# design.net
KiCad netlist of a schematic drawn in EasyEDA
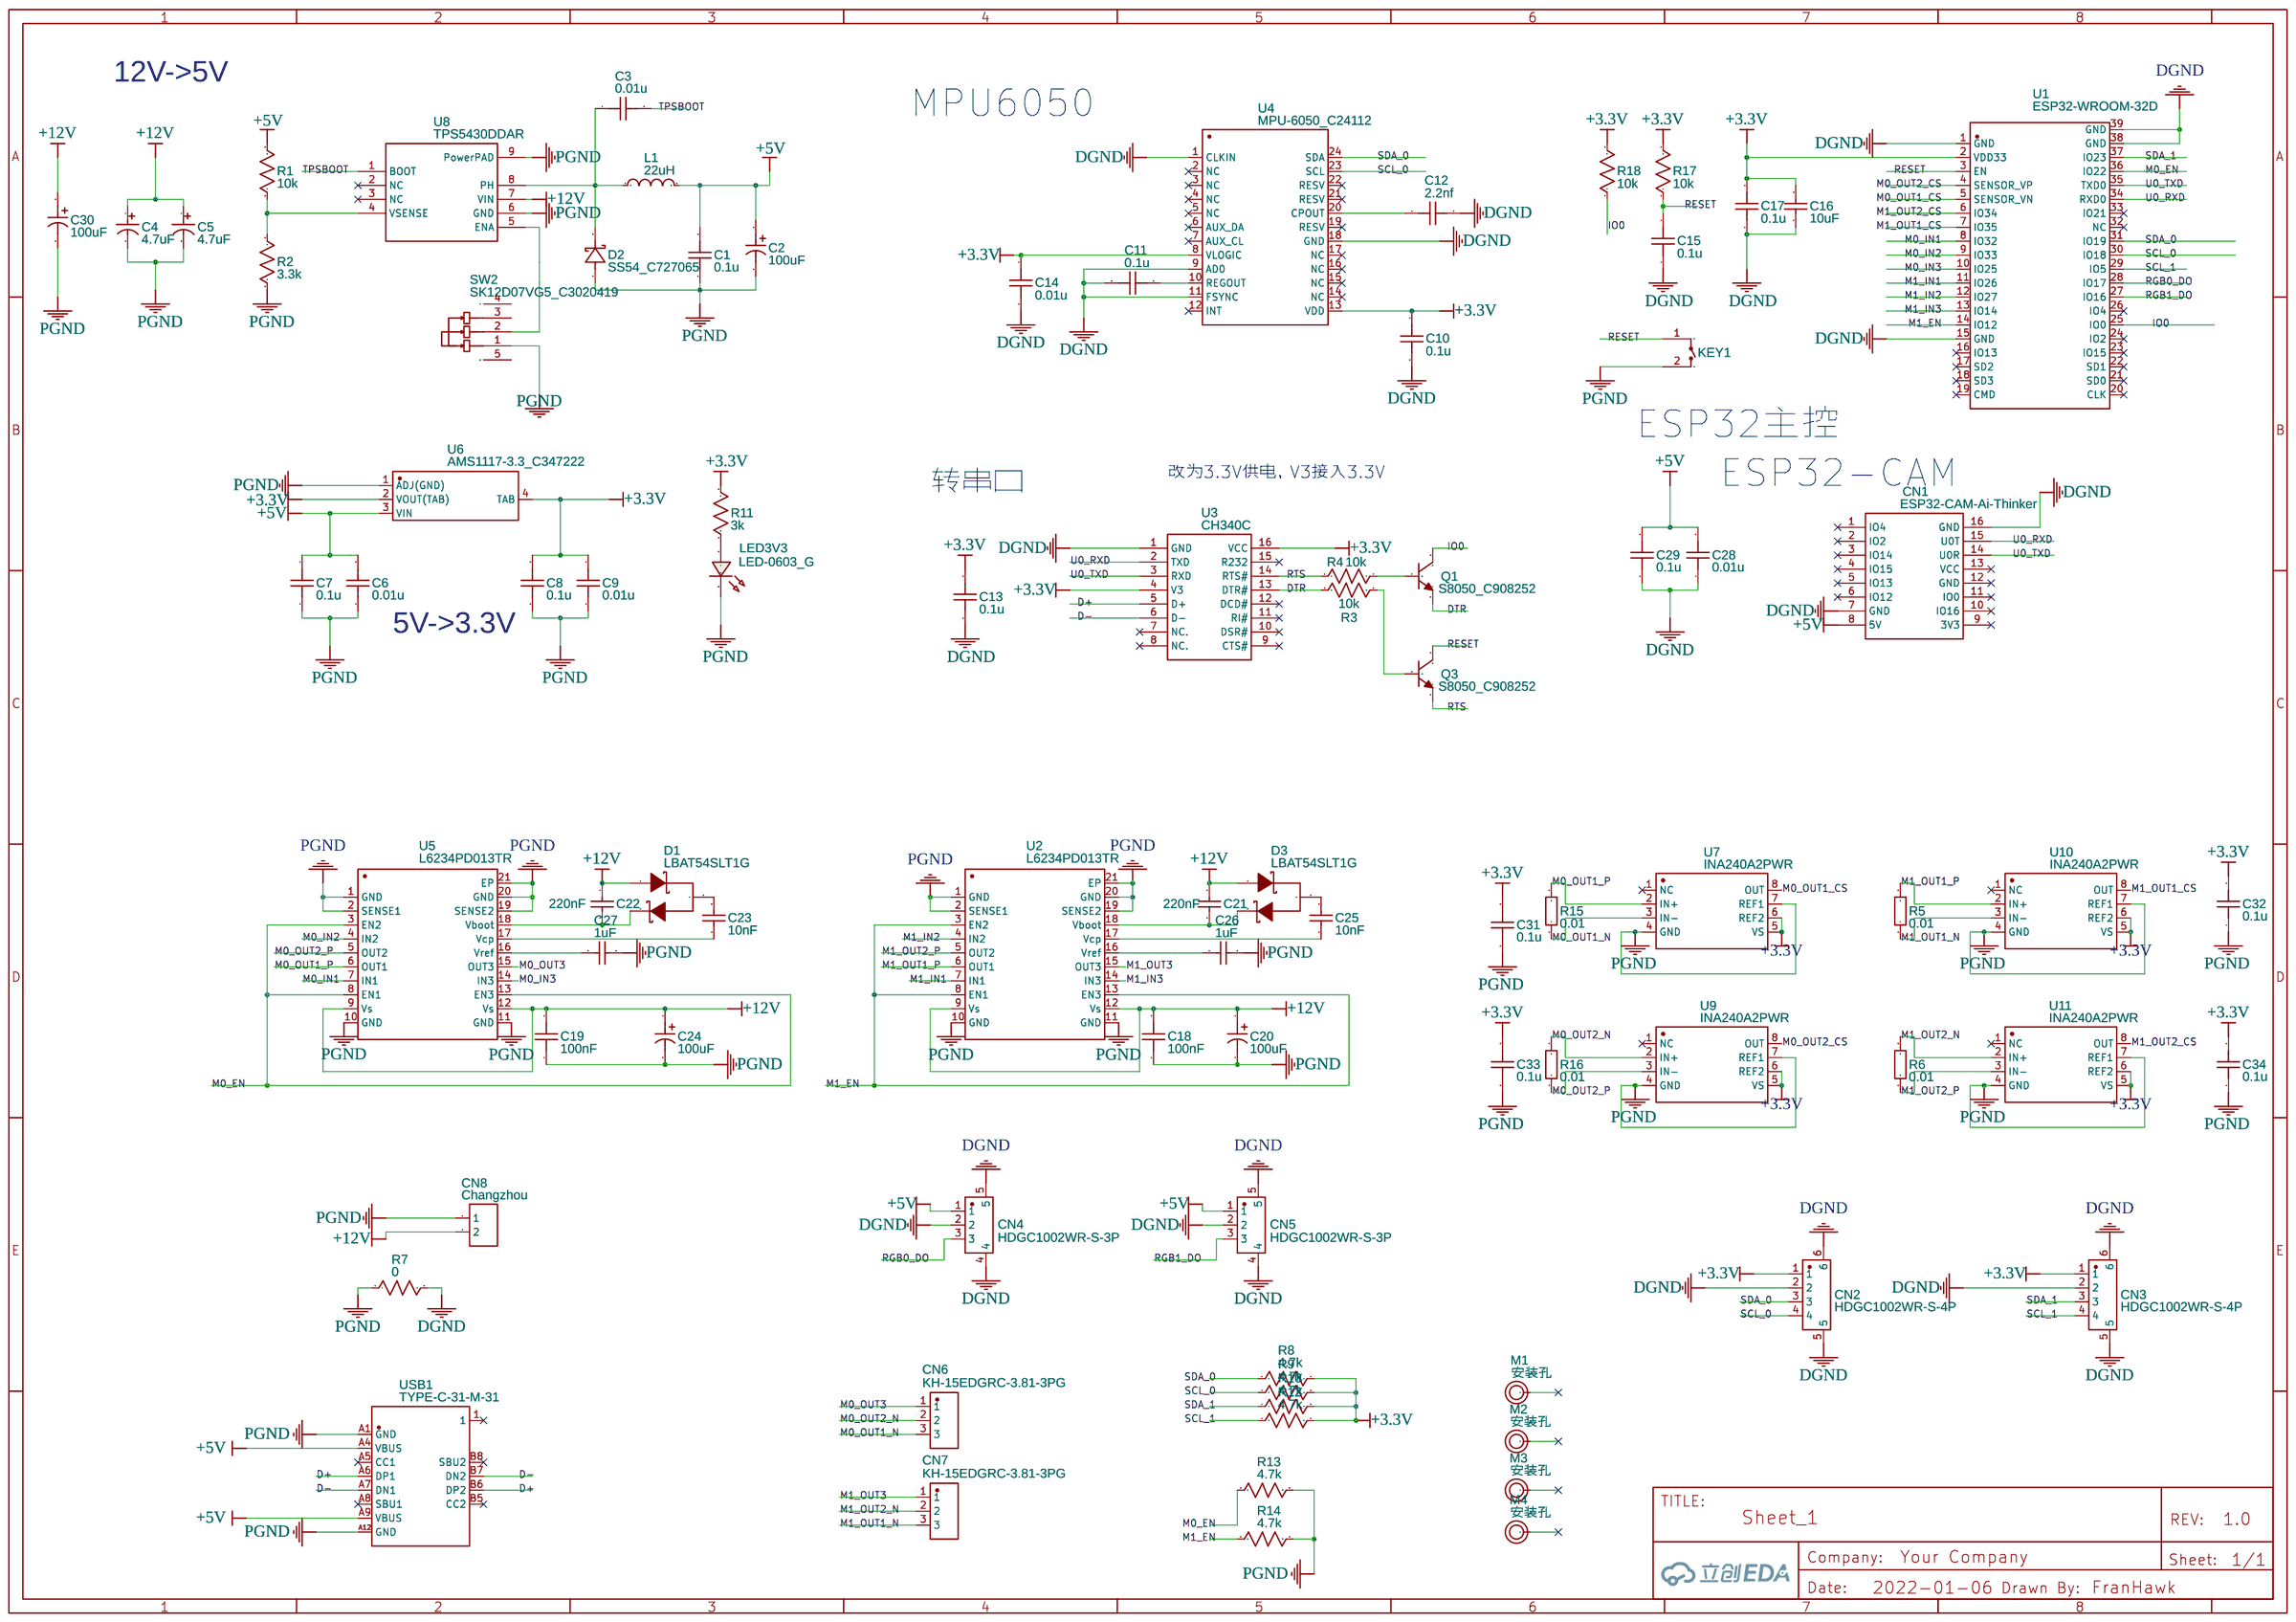
[diagram p0: schematic sheet]

(export (version "E")
  (design (tool "Eeschema 10.0.6"))
  (components
    (comp (ref "C1") (value "0.1u") (libsource (lib "") (part "C_0603_US")))
    (comp (ref "C2")
      (value "100uF")
      (fields
        (field (name "BOM_Manufacturer Part") "LZ101M0801013PE3")
        (field (name "BOM_Supplier Part") "C2847237")
      )
      (libsource (lib "") (part "LZ101M0801013PE3"))
    )
    (comp (ref "C3") (value "0.01u") (libsource (lib "") (part "C_0603_US_1")))
    (comp (ref "C4")
      (value "4.7uF")
      (fields
        (field (name "BOM_Manufacturer Part") "4.7uF 50V 5*11")
        (field (name "BOM_Supplier Part") "C43344")
      )
      (libsource (lib "") (part "4.7uF 50V 5*11"))
    )
    (comp (ref "C5")
      (value "4.7uF")
      (fields
        (field (name "BOM_Manufacturer Part") "4.7uF 50V 5*11")
        (field (name "BOM_Supplier Part") "C43344")
      )
      (libsource (lib "") (part "4.7uF 50V 5*11"))
    )
    (comp (ref "C6") (value "0.01u") (libsource (lib "") (part "C_0603_US")))
    (comp (ref "C7") (value "0.1u") (libsource (lib "") (part "C_0603_US")))
    (comp (ref "C8") (value "0.1u") (libsource (lib "") (part "C_0603_US")))
    (comp (ref "C9") (value "0.01u") (libsource (lib "") (part "C_0603_US")))
    (comp (ref "C10") (value "0.1u") (libsource (lib "") (part "C_0603_US_3")))
    (comp (ref "C11") (value "0.1u") (libsource (lib "") (part "C_0603_US_2")))
    (comp (ref "C12") (value "2.2nf") (libsource (lib "") (part "C_0603_US_1")))
    (comp (ref "C13") (value "0.1u") (libsource (lib "") (part "C_0603_US")))
    (comp (ref "C14") (value "0.01u") (libsource (lib "") (part "C_0603_US_3")))
    (comp (ref "C15") (value "0.1u") (libsource (lib "") (part "C_0603_US")))
    (comp (ref "C16")
      (value "10uF")
      (fields
        (field (name "BOM_Manufacturer Part") "CL31A106KAHNNNE")
        (field (name "BOM_Supplier Part") "C9807")
      )
      (libsource (lib "") (part "CL31A106KAHNNNE"))
    )
    (comp (ref "C17") (value "0.1u") (libsource (lib "") (part "C_0603_US")))
    (comp (ref "C18")
      (value "100nF")
      (fields
        (field (name "BOM_Manufacturer Part") "C0805X104K101T")
        (field (name "BOM_Supplier Part") "C485772")
      )
      (libsource (lib "") (part "C0805X104K101T_C485772"))
    )
    (comp (ref "C19")
      (value "100nF")
      (fields
        (field (name "BOM_Manufacturer Part") "C0805X104K101T")
        (field (name "BOM_Supplier Part") "C485772")
      )
      (libsource (lib "") (part "C0805X104K101T_C485772"))
    )
    (comp (ref "C20")
      (value "100uF")
      (fields
        (field (name "BOM_Manufacturer Part") "LZ101M0801013PE3")
        (field (name "BOM_Supplier Part") "C2847237")
      )
      (libsource (lib "") (part "LZ101M0801013PE3"))
    )
    (comp (ref "C21")
      (value "220nF")
      (fields
        (field (name "BOM_Manufacturer Part") "CL21B224KBFNNNE")
        (field (name "BOM_Supplier Part") "C5378")
      )
      (libsource (lib "") (part "CL21B224KBFNNNE"))
    )
    (comp (ref "C22")
      (value "220nF")
      (fields
        (field (name "BOM_Manufacturer Part") "CL21B224KBFNNNE")
        (field (name "BOM_Supplier Part") "C5378")
      )
      (libsource (lib "") (part "CL21B224KBFNNNE"))
    )
    (comp (ref "C23")
      (value "10nF")
      (fields
        (field (name "BOM_Manufacturer Part") "CL21A106KAYNNNE")
        (field (name "BOM_Supplier Part") "C15850")
      )
      (libsource (lib "") (part "CL21A106KAYNNNE"))
    )
    (comp (ref "C24")
      (value "100uF")
      (fields
        (field (name "BOM_Manufacturer Part") "LZ101M0801013PE3")
        (field (name "BOM_Supplier Part") "C2847237")
      )
      (libsource (lib "") (part "LZ101M0801013PE3"))
    )
    (comp (ref "C25")
      (value "10nF")
      (fields
        (field (name "BOM_Manufacturer Part") "CL21A106KAYNNNE")
        (field (name "BOM_Supplier Part") "C15850")
      )
      (libsource (lib "") (part "CL21A106KAYNNNE"))
    )
    (comp (ref "C26")
      (value "1uF")
      (fields
        (field (name "BOM_Manufacturer Part") "CL21B105KBFNNNE")
        (field (name "BOM_Supplier Part") "C28323")
      )
      (libsource (lib "") (part "CL21B105KBFNNNE"))
    )
    (comp (ref "C27")
      (value "1uF")
      (fields
        (field (name "BOM_Manufacturer Part") "CL21B105KBFNNNE")
        (field (name "BOM_Supplier Part") "C28323")
      )
      (libsource (lib "") (part "CL21B105KBFNNNE"))
    )
    (comp (ref "C28") (value "0.01u") (libsource (lib "") (part "C_0603_US")))
    (comp (ref "C29") (value "0.1u") (libsource (lib "") (part "C_0603_US")))
    (comp (ref "C30")
      (value "100uF")
      (fields
        (field (name "BOM_Manufacturer Part") "LZ101M0801013PE3")
        (field (name "BOM_Supplier Part") "C2847237")
      )
      (libsource (lib "") (part "LZ101M0801013PE3"))
    )
    (comp (ref "C31") (value "0.1u") (libsource (lib "") (part "C_0603_US")))
    (comp (ref "C32") (value "0.1u") (libsource (lib "") (part "C_0603_US")))
    (comp (ref "C33") (value "0.1u") (libsource (lib "") (part "C_0603_US")))
    (comp (ref "C34") (value "0.1u") (libsource (lib "") (part "C_0603_US")))
    (comp (ref "CN1")
      (value "ESP32-CAM-Ai-Thinker")
      (fields (field (name "BOM_Manufacturer Part") "ESP32-CAM"))
      (libsource (lib "") (part "ESP32-CAM-Ai-Thinker"))
    )
    (comp (ref "CN2")
      (value "HDGC1002WR-S-4P")
      (fields (field (name "BOM_Supplier Part") "C2936214"))
      (libsource (lib "") (part "HDGC1002WR-S-4P"))
    )
    (comp (ref "CN3")
      (value "HDGC1002WR-S-4P")
      (fields (field (name "BOM_Supplier Part") "C2936214"))
      (libsource (lib "") (part "HDGC1002WR-S-4P"))
    )
    (comp (ref "CN4")
      (value "HDGC1002WR-S-3P")
      (fields (field (name "BOM_Supplier Part") "C2936213"))
      (libsource (lib "") (part "HDGC1002WR-S-3P"))
    )
    (comp (ref "CN5")
      (value "HDGC1002WR-S-3P")
      (fields (field (name "BOM_Supplier Part") "C2936213"))
      (libsource (lib "") (part "HDGC1002WR-S-3P"))
    )
    (comp (ref "CN6")
      (value "KH-15EDGRC-3.81-3PG")
      (fields (field (name "BOM_Supplier Part") "C2761212"))
      (libsource (lib "") (part "KH-15EDGRC-3.81-3PG"))
    )
    (comp (ref "CN7")
      (value "KH-15EDGRC-3.81-3PG")
      (fields (field (name "BOM_Supplier Part") "C2761212"))
      (libsource (lib "") (part "KH-15EDGRC-3.81-3PG"))
    )
    (comp (ref "CN8")
      (value "Changzhou")
      (fields (field (name "BOM_Manufacturer Part") "XT30UPB-F") (field (name "BOM_Supplier Part") "C108769"))
      (libsource (lib "") (part "XT30UPB-F"))
    )
    (comp (ref "D1")
      (value "LBAT54SLT1G")
      (fields (field (name "BOM_Supplier Part") "C12765"))
      (libsource (lib "") (part "LBAT54SLT1G"))
    )
    (comp (ref "D2")
      (value "SS54_C727065")
      (fields (field (name "BOM_Manufacturer Part") "SS54") (field (name "BOM_Supplier Part") "C727065"))
      (libsource (lib "") (part "SS54_C727065"))
    )
    (comp (ref "D3")
      (value "LBAT54SLT1G")
      (fields (field (name "BOM_Supplier Part") "C12765"))
      (libsource (lib "") (part "LBAT54SLT1G"))
    )
    (comp (ref "KEY1")
      (value "TS-1101S-B-B-B-W-A")
      (fields (field (name "BOM_Supplier Part") "C692465"))
      (libsource (lib "") (part "TS-1101S-B-B-B-W-A"))
    )
    (comp (ref "L1")
      (value "22uH")
      (fields
        (field (name "BOM_Manufacturer Part") "SM3521-220MT")
        (field (name "BOM_Supplier Part") "C68387")
      )
      (libsource (lib "") (part "SM3521-220MT"))
    )
    (comp (ref "LED3V3")
      (value "LED-0603_G")
      (fields
        (field (name "BOM_Manufacturer Part") "19-217/GHC-YR1S2/3T")
        (field (name "BOM_Supplier Part") "C72043")
      )
      (libsource (lib "") (part "LED-0603_G"))
    )
    (comp (ref "M1") (value "安装孔") (libsource (lib "") (part "安装孔")))
    (comp (ref "M2") (value "安装孔") (libsource (lib "") (part "安装孔")))
    (comp (ref "M3") (value "安装孔") (libsource (lib "") (part "安装孔")))
    (comp (ref "M4") (value "安装孔") (libsource (lib "") (part "安装孔")))
    (comp (ref "Q1")
      (value "S8050_C908252")
      (fields (field (name "BOM_Manufacturer Part") "S8050") (field (name "BOM_Supplier Part") "C908252"))
      (libsource (lib "") (part "S8050_C908252"))
    )
    (comp (ref "Q3")
      (value "S8050_C908252")
      (fields (field (name "BOM_Manufacturer Part") "S8050") (field (name "BOM_Supplier Part") "C908252"))
      (libsource (lib "") (part "S8050_C908252"))
    )
    (comp (ref "R1") (value "10k") (libsource (lib "") (part "R_0603_US")))
    (comp (ref "R2") (value "3.3k") (libsource (lib "") (part "R_0603_US")))
    (comp (ref "R3") (value "10k") (libsource (lib "") (part "R_0603_US_1")))
    (comp (ref "R4") (value "10k") (libsource (lib "") (part "R_0603_US_1")))
    (comp (ref "R5")
      (value "0.01")
      (fields
        (field (name "BOM_Manufacturer Part") "RTT06R010FTP")
        (field (name "BOM_Supplier Part") "C104920")
      )
      (libsource (lib "") (part "RTT06R010FTP"))
    )
    (comp (ref "R6")
      (value "0.01")
      (fields
        (field (name "BOM_Manufacturer Part") "RTT06R010FTP")
        (field (name "BOM_Supplier Part") "C104920")
      )
      (libsource (lib "") (part "RTT06R010FTP"))
    )
    (comp (ref "R7") (value "0") (libsource (lib "") (part "R_0603_US_1")))
    (comp (ref "R8") (value "4.7k") (libsource (lib "") (part "R_0603_US_1")))
    (comp (ref "R9") (value "4.7k") (libsource (lib "") (part "R_0603_US_1")))
    (comp (ref "R10") (value "4.7k") (libsource (lib "") (part "R_0603_US_1")))
    (comp (ref "R11") (value "3k") (libsource (lib "") (part "R_0603_US")))
    (comp (ref "R12") (value "4.7k") (libsource (lib "") (part "R_0603_US_1")))
    (comp (ref "R13") (value "4.7k") (libsource (lib "") (part "R_0603_US_1")))
    (comp (ref "R14") (value "4.7k") (libsource (lib "") (part "R_0603_US_1")))
    (comp (ref "R15")
      (value "0.01")
      (fields
        (field (name "BOM_Manufacturer Part") "RTT06R010FTP")
        (field (name "BOM_Supplier Part") "C104920")
      )
      (libsource (lib "") (part "RTT06R010FTP"))
    )
    (comp (ref "R16")
      (value "0.01")
      (fields
        (field (name "BOM_Manufacturer Part") "RTT06R010FTP")
        (field (name "BOM_Supplier Part") "C104920")
      )
      (libsource (lib "") (part "RTT06R010FTP"))
    )
    (comp (ref "R17") (value "10k") (libsource (lib "") (part "R_0603_US")))
    (comp (ref "R18") (value "10k") (libsource (lib "") (part "R_0603_US")))
    (comp (ref "SW2")
      (value "SK12D07VG5_C3020419")
      (fields
        (field (name "BOM_Manufacturer Part") "SK12D07VG5")
        (field (name "BOM_Supplier Part") "C3020419")
      )
      (libsource (lib "") (part "SK12D07VG5_C3020419"))
    )
    (comp (ref "U1")
      (value "ESP32-WROOM-32D")
      (fields (field (name "BOM_Supplier Part") "C473012"))
      (libsource (lib "") (part "ESP32-WROOM-32D"))
    )
    (comp (ref "U2")
      (value "L6234PD013TR")
      (fields (field (name "BOM_Supplier Part") "C77581"))
      (libsource (lib "") (part "L6234PD013TR"))
    )
    (comp (ref "U3")
      (value "CH340C")
      (fields (field (name "BOM_Supplier Part") "C84681"))
      (libsource (lib "") (part "CH340C"))
    )
    (comp (ref "U4")
      (value "MPU-6050_C24112")
      (fields (field (name "BOM_Manufacturer Part") "MPU-6050") (field (name "BOM_Supplier Part") "C24112"))
      (libsource (lib "") (part "MPU-6050_C24112"))
    )
    (comp (ref "U5")
      (value "L6234PD013TR")
      (fields (field (name "BOM_Supplier Part") "C77581"))
      (libsource (lib "") (part "L6234PD013TR"))
    )
    (comp (ref "U6")
      (value "AMS1117-3.3_C347222")
      (fields
        (field (name "BOM_Manufacturer Part") "AMS1117-3.3")
        (field (name "BOM_Supplier Part") "C347222")
      )
      (libsource (lib "") (part "AMS1117-3.3_C347222"))
    )
    (comp (ref "U7")
      (value "INA240A2PWR")
      (fields (field (name "BOM_Supplier Part") "C129949"))
      (libsource (lib "") (part "INA240A2PWR"))
    )
    (comp (ref "U8")
      (value "TPS5430DDAR")
      (fields (field (name "BOM_Supplier Part") "C9864"))
      (libsource (lib "") (part "TPS5430DDAR"))
    )
    (comp (ref "U9")
      (value "INA240A2PWR")
      (fields (field (name "BOM_Supplier Part") "C129949"))
      (libsource (lib "") (part "INA240A2PWR"))
    )
    (comp (ref "U10")
      (value "INA240A2PWR")
      (fields (field (name "BOM_Supplier Part") "C129949"))
      (libsource (lib "") (part "INA240A2PWR"))
    )
    (comp (ref "U11")
      (value "INA240A2PWR")
      (fields (field (name "BOM_Supplier Part") "C129949"))
      (libsource (lib "") (part "INA240A2PWR"))
    )
    (comp (ref "USB1")
      (value "TYPE-C-31-M-31")
      (fields (field (name "BOM_Supplier Part") "C2760486"))
      (libsource (lib "") (part "TYPE-C-31-M-31"))
    )
  )
  (nets
    (net (code "1") (name "+3.3V") (class "Default")
      (node (ref "C10") (pin "1") (pinfunction "1_1") (pintype "unspecified"))
      (node (ref "C13") (pin "2") (pinfunction "2_2") (pintype "unspecified"))
      (node (ref "C14") (pin "1") (pinfunction "1_1") (pintype "unspecified"))
      (node (ref "C16") (pin "2") (pinfunction "2_2") (pintype "input"))
      (node (ref "C17") (pin "2") (pinfunction "2_2") (pintype "unspecified"))
      (node (ref "C31") (pin "2") (pinfunction "2_2") (pintype "unspecified"))
      (node (ref "C32") (pin "2") (pinfunction "2_2") (pintype "unspecified"))
      (node (ref "C33") (pin "2") (pinfunction "2_2") (pintype "unspecified"))
      (node (ref "C34") (pin "2") (pinfunction "2_2") (pintype "unspecified"))
      (node (ref "C8") (pin "2") (pinfunction "2_2") (pintype "unspecified"))
      (node (ref "C9") (pin "2") (pinfunction "2_2") (pintype "unspecified"))
      (node (ref "CN2") (pin "1") (pinfunction "1_1") (pintype "unspecified"))
      (node (ref "CN3") (pin "1") (pinfunction "1_1") (pintype "unspecified"))
      (node (ref "R10") (pin "2") (pinfunction "2_2") (pintype "unspecified"))
      (node (ref "R11") (pin "2") (pinfunction "2_2") (pintype "unspecified"))
      (node (ref "R12") (pin "2") (pinfunction "2_2") (pintype "unspecified"))
      (node (ref "R17") (pin "2") (pinfunction "2_2") (pintype "unspecified"))
      (node (ref "R18") (pin "2") (pinfunction "2_2") (pintype "unspecified"))
      (node (ref "R8") (pin "2") (pinfunction "2_2") (pintype "unspecified"))
      (node (ref "R9") (pin "2") (pinfunction "2_2") (pintype "unspecified"))
      (node (ref "U1") (pin "2") (pinfunction "VDD33_2") (pintype "unspecified"))
      (node (ref "U10") (pin "5") (pinfunction "VS_5") (pintype "unspecified"))
      (node (ref "U10") (pin "6") (pinfunction "REF2_6") (pintype "unspecified"))
      (node (ref "U11") (pin "5") (pinfunction "VS_5") (pintype "unspecified"))
      (node (ref "U11") (pin "6") (pinfunction "REF2_6") (pintype "unspecified"))
      (node (ref "U3") (pin "16") (pinfunction "VCC_16") (pintype "unspecified"))
      (node (ref "U3") (pin "4") (pinfunction "V3_4") (pintype "unspecified"))
      (node (ref "U4") (pin "13") (pinfunction "VDD_13") (pintype "unspecified"))
      (node (ref "U4") (pin "8") (pinfunction "VLOGIC_8") (pintype "unspecified"))
      (node (ref "U6") (pin "2") (pinfunction "VOUT(TAB)_2") (pintype "unspecified"))
      (node (ref "U6") (pin "4") (pinfunction "TAB_4") (pintype "unspecified"))
      (node (ref "U7") (pin "5") (pinfunction "VS_5") (pintype "unspecified"))
      (node (ref "U7") (pin "6") (pinfunction "REF2_6") (pintype "unspecified"))
      (node (ref "U9") (pin "5") (pinfunction "VS_5") (pintype "unspecified"))
      (node (ref "U9") (pin "6") (pinfunction "REF2_6") (pintype "unspecified"))
    )
    (net (code "2") (name "+5V") (class "Default")
      (node (ref "C1") (pin "2") (pinfunction "2_2") (pintype "unspecified"))
      (node (ref "C2") (pin "1") (pinfunction "1_1") (pintype "input"))
      (node (ref "C28") (pin "2") (pinfunction "2_2") (pintype "unspecified"))
      (node (ref "C29") (pin "2") (pinfunction "2_2") (pintype "unspecified"))
      (node (ref "C6") (pin "2") (pinfunction "2_2") (pintype "unspecified"))
      (node (ref "C7") (pin "2") (pinfunction "2_2") (pintype "unspecified"))
      (node (ref "CN1") (pin "8") (pinfunction "5V_8") (pintype "unspecified"))
      (node (ref "CN4") (pin "1") (pinfunction "1_1") (pintype "unspecified"))
      (node (ref "CN5") (pin "1") (pinfunction "1_1") (pintype "unspecified"))
      (node (ref "L1") (pin "2") (pinfunction "2_2") (pintype "unspecified"))
      (node (ref "R1") (pin "2") (pinfunction "2_2") (pintype "unspecified"))
      (node (ref "U6") (pin "3") (pinfunction "VIN_3") (pintype "unspecified"))
      (node (ref "USB1") (pin "A4") (pinfunction "VBUS_A4") (pintype "unspecified"))
      (node (ref "USB1") (pin "A9") (pinfunction "VBUS_A9") (pintype "unspecified"))
    )
    (net (code "3") (name "+12V") (class "Default")
      (node (ref "C18") (pin "2") (pinfunction "2_2") (pintype "unspecified"))
      (node (ref "C19") (pin "2") (pinfunction "2_2") (pintype "unspecified"))
      (node (ref "C20") (pin "1") (pinfunction "1_1") (pintype "input"))
      (node (ref "C21") (pin "1") (pinfunction "1_1") (pintype "input"))
      (node (ref "C22") (pin "1") (pinfunction "1_1") (pintype "input"))
      (node (ref "C24") (pin "1") (pinfunction "1_1") (pintype "input"))
      (node (ref "C30") (pin "1") (pinfunction "1_1") (pintype "input"))
      (node (ref "C4") (pin "1") (pinfunction "1_1") (pintype "input"))
      (node (ref "C5") (pin "1") (pinfunction "1_1") (pintype "input"))
      (node (ref "CN8") (pin "2") (pinfunction "2_2") (pintype "unspecified"))
      (node (ref "D1") (pin "1") (pinfunction "A_1") (pintype "unspecified"))
      (node (ref "D3") (pin "1") (pinfunction "A_1") (pintype "unspecified"))
      (node (ref "U2") (pin "12") (pinfunction "Vs_12") (pintype "unspecified"))
      (node (ref "U2") (pin "9") (pinfunction "Vs_9") (pintype "unspecified"))
      (node (ref "U5") (pin "12") (pinfunction "Vs_12") (pintype "unspecified"))
      (node (ref "U5") (pin "9") (pinfunction "Vs_9") (pintype "unspecified"))
      (node (ref "U8") (pin "7") (pinfunction "VIN_7") (pintype "unspecified"))
    )
    (net (code "4") (name "/D+") (class "Default")
      (node (ref "U3") (pin "5") (pinfunction "D+_5") (pintype "unspecified"))
      (node (ref "USB1") (pin "A6") (pinfunction "DP1_A6") (pintype "unspecified"))
      (node (ref "USB1") (pin "B6") (pinfunction "DP2_B6") (pintype "unspecified"))
    )
    (net (code "5") (name "/D-") (class "Default")
      (node (ref "U3") (pin "6") (pinfunction "D-_6") (pintype "unspecified"))
      (node (ref "USB1") (pin "A7") (pinfunction "DN1_A7") (pintype "unspecified"))
      (node (ref "USB1") (pin "B7") (pinfunction "DN2_B7") (pintype "unspecified"))
    )
    (net (code "6") (name "/DTR") (class "Default")
      (node (ref "Q1") (pin "2") (pinfunction "E_2") (pintype "input"))
      (node (ref "R3") (pin "1") (pinfunction "1_1") (pintype "unspecified"))
      (node (ref "U3") (pin "13") (pinfunction "DTR#_13") (pintype "unspecified"))
    )
    (net (code "7") (name "/IO0") (class "Default")
      (node (ref "Q1") (pin "3") (pinfunction "C_3") (pintype "input"))
      (node (ref "R18") (pin "1") (pinfunction "1_1") (pintype "unspecified"))
      (node (ref "U1") (pin "25") (pinfunction "IO0_25") (pintype "unspecified"))
    )
    (net (code "8") (name "/M0_EN") (class "Default")
      (node (ref "R13") (pin "1") (pinfunction "1_1") (pintype "unspecified"))
      (node (ref "U1") (pin "36") (pinfunction "IO22_36") (pintype "unspecified"))
      (node (ref "U5") (pin "13") (pinfunction "EN3_13") (pintype "unspecified"))
      (node (ref "U5") (pin "3") (pinfunction "EN2_3") (pintype "unspecified"))
      (node (ref "U5") (pin "8") (pinfunction "EN1_8") (pintype "unspecified"))
    )
    (net (code "9") (name "/M0_IN1") (class "Default")
      (node (ref "U1") (pin "8") (pinfunction "IO32_8") (pintype "unspecified"))
      (node (ref "U5") (pin "7") (pinfunction "IN1_7") (pintype "unspecified"))
    )
    (net (code "10") (name "/M0_IN2") (class "Default")
      (node (ref "U1") (pin "9") (pinfunction "IO33_9") (pintype "unspecified"))
      (node (ref "U5") (pin "4") (pinfunction "IN2_4") (pintype "unspecified"))
    )
    (net (code "11") (name "/M0_IN3") (class "Default")
      (node (ref "U1") (pin "10") (pinfunction "IO25_10") (pintype "unspecified"))
      (node (ref "U5") (pin "14") (pinfunction "IN3_14") (pintype "unspecified"))
    )
    (net (code "12") (name "/M0_OUT1_CS") (class "Default")
      (node (ref "U1") (pin "5") (pinfunction "SENSOR_VN_5") (pintype "unspecified"))
      (node (ref "U7") (pin "8") (pinfunction "OUT_8") (pintype "unspecified"))
    )
    (net (code "13") (name "/M0_OUT1_N") (class "Default")
      (node (ref "CN6") (pin "3") (pinfunction "3_3") (pintype "unspecified"))
      (node (ref "R15") (pin "1") (pinfunction "1_1") (pintype "unspecified"))
      (node (ref "U7") (pin "3") (pinfunction "IN-_3") (pintype "unspecified"))
    )
    (net (code "14") (name "/M0_OUT1_P") (class "Default")
      (node (ref "R15") (pin "2") (pinfunction "2_2") (pintype "unspecified"))
      (node (ref "U5") (pin "6") (pinfunction "OUT1_6") (pintype "unspecified"))
      (node (ref "U7") (pin "2") (pinfunction "IN+_2") (pintype "unspecified"))
    )
    (net (code "15") (name "/M0_OUT2_CS") (class "Default")
      (node (ref "U1") (pin "4") (pinfunction "SENSOR_VP_4") (pintype "unspecified"))
      (node (ref "U9") (pin "8") (pinfunction "OUT_8") (pintype "unspecified"))
    )
    (net (code "16") (name "/M0_OUT2_N") (class "Default")
      (node (ref "CN6") (pin "2") (pinfunction "2_2") (pintype "unspecified"))
      (node (ref "R16") (pin "2") (pinfunction "2_2") (pintype "unspecified"))
      (node (ref "U9") (pin "2") (pinfunction "IN+_2") (pintype "unspecified"))
    )
    (net (code "17") (name "/M0_OUT2_P") (class "Default")
      (node (ref "R16") (pin "1") (pinfunction "1_1") (pintype "unspecified"))
      (node (ref "U5") (pin "5") (pinfunction "OUT2_5") (pintype "unspecified"))
      (node (ref "U9") (pin "3") (pinfunction "IN-_3") (pintype "unspecified"))
    )
    (net (code "18") (name "/M0_OUT3") (class "Default")
      (node (ref "CN6") (pin "1") (pinfunction "1_1") (pintype "unspecified"))
      (node (ref "U5") (pin "15") (pinfunction "OUT3_15") (pintype "unspecified"))
    )
    (net (code "19") (name "/M1_EN") (class "Default")
      (node (ref "R14") (pin "1") (pinfunction "1_1") (pintype "unspecified"))
      (node (ref "U1") (pin "14") (pinfunction "IO12_14") (pintype "unspecified"))
      (node (ref "U2") (pin "13") (pinfunction "EN3_13") (pintype "unspecified"))
      (node (ref "U2") (pin "3") (pinfunction "EN2_3") (pintype "unspecified"))
      (node (ref "U2") (pin "8") (pinfunction "EN1_8") (pintype "unspecified"))
    )
    (net (code "20") (name "/M1_IN1") (class "Default")
      (node (ref "U1") (pin "11") (pinfunction "IO26_11") (pintype "unspecified"))
      (node (ref "U2") (pin "7") (pinfunction "IN1_7") (pintype "unspecified"))
    )
    (net (code "21") (name "/M1_IN2") (class "Default")
      (node (ref "U1") (pin "12") (pinfunction "IO27_12") (pintype "unspecified"))
      (node (ref "U2") (pin "4") (pinfunction "IN2_4") (pintype "unspecified"))
    )
    (net (code "22") (name "/M1_IN3") (class "Default")
      (node (ref "U1") (pin "13") (pinfunction "IO14_13") (pintype "unspecified"))
      (node (ref "U2") (pin "14") (pinfunction "IN3_14") (pintype "unspecified"))
    )
    (net (code "23") (name "/M1_OUT1_CS") (class "Default")
      (node (ref "U1") (pin "7") (pinfunction "IO35_7") (pintype "unspecified"))
      (node (ref "U10") (pin "8") (pinfunction "OUT_8") (pintype "unspecified"))
    )
    (net (code "24") (name "/M1_OUT1_N") (class "Default")
      (node (ref "CN7") (pin "3") (pinfunction "3_3") (pintype "unspecified"))
      (node (ref "R5") (pin "1") (pinfunction "1_1") (pintype "unspecified"))
      (node (ref "U10") (pin "3") (pinfunction "IN-_3") (pintype "unspecified"))
    )
    (net (code "25") (name "/M1_OUT1_P") (class "Default")
      (node (ref "R5") (pin "2") (pinfunction "2_2") (pintype "unspecified"))
      (node (ref "U10") (pin "2") (pinfunction "IN+_2") (pintype "unspecified"))
      (node (ref "U2") (pin "6") (pinfunction "OUT1_6") (pintype "unspecified"))
    )
    (net (code "26") (name "/M1_OUT2_CS") (class "Default")
      (node (ref "U1") (pin "6") (pinfunction "IO34_6") (pintype "unspecified"))
      (node (ref "U11") (pin "8") (pinfunction "OUT_8") (pintype "unspecified"))
    )
    (net (code "27") (name "/M1_OUT2_N") (class "Default")
      (node (ref "CN7") (pin "2") (pinfunction "2_2") (pintype "unspecified"))
      (node (ref "R6") (pin "2") (pinfunction "2_2") (pintype "unspecified"))
      (node (ref "U11") (pin "2") (pinfunction "IN+_2") (pintype "unspecified"))
    )
    (net (code "28") (name "/M1_OUT2_P") (class "Default")
      (node (ref "R6") (pin "1") (pinfunction "1_1") (pintype "unspecified"))
      (node (ref "U11") (pin "3") (pinfunction "IN-_3") (pintype "unspecified"))
      (node (ref "U2") (pin "5") (pinfunction "OUT2_5") (pintype "unspecified"))
    )
    (net (code "29") (name "/M1_OUT3") (class "Default")
      (node (ref "CN7") (pin "1") (pinfunction "1_1") (pintype "unspecified"))
      (node (ref "U2") (pin "15") (pinfunction "OUT3_15") (pintype "unspecified"))
    )
    (net (code "30") (name "/RESET") (class "Default")
      (node (ref "C15") (pin "2") (pinfunction "2_2") (pintype "unspecified"))
      (node (ref "KEY1") (pin "1") (pinfunction "1_1") (pintype "unspecified"))
      (node (ref "Q3") (pin "3") (pinfunction "C_3") (pintype "input"))
      (node (ref "R17") (pin "1") (pinfunction "1_1") (pintype "unspecified"))
      (node (ref "U1") (pin "3") (pinfunction "EN_3") (pintype "unspecified"))
    )
    (net (code "31") (name "/RGB0_DO") (class "Default")
      (node (ref "CN4") (pin "3") (pinfunction "3_3") (pintype "unspecified"))
      (node (ref "U1") (pin "28") (pinfunction "IO17_28") (pintype "unspecified"))
    )
    (net (code "32") (name "/RGB1_DO") (class "Default")
      (node (ref "CN5") (pin "3") (pinfunction "3_3") (pintype "unspecified"))
      (node (ref "U1") (pin "27") (pinfunction "IO16_27") (pintype "unspecified"))
    )
    (net (code "33") (name "/RTS") (class "Default")
      (node (ref "Q3") (pin "2") (pinfunction "E_2") (pintype "input"))
      (node (ref "R4") (pin "1") (pinfunction "1_1") (pintype "unspecified"))
      (node (ref "U3") (pin "14") (pinfunction "RTS#_14") (pintype "unspecified"))
    )
    (net (code "34") (name "/SCL_0") (class "Default")
      (node (ref "CN2") (pin "4") (pinfunction "4_4") (pintype "unspecified"))
      (node (ref "R9") (pin "1") (pinfunction "1_1") (pintype "unspecified"))
      (node (ref "U1") (pin "30") (pinfunction "IO18_30") (pintype "unspecified"))
      (node (ref "U4") (pin "23") (pinfunction "SCL_23") (pintype "unspecified"))
    )
    (net (code "35") (name "/SCL_1") (class "Default")
      (node (ref "CN3") (pin "4") (pinfunction "4_4") (pintype "unspecified"))
      (node (ref "R12") (pin "1") (pinfunction "1_1") (pintype "unspecified"))
      (node (ref "U1") (pin "29") (pinfunction "IO5_29") (pintype "unspecified"))
    )
    (net (code "36") (name "/SDA_0") (class "Default")
      (node (ref "CN2") (pin "3") (pinfunction "3_3") (pintype "unspecified"))
      (node (ref "R8") (pin "1") (pinfunction "1_1") (pintype "unspecified"))
      (node (ref "U1") (pin "31") (pinfunction "IO19_31") (pintype "unspecified"))
      (node (ref "U4") (pin "24") (pinfunction "SDA_24") (pintype "unspecified"))
    )
    (net (code "37") (name "/SDA_1") (class "Default")
      (node (ref "CN3") (pin "3") (pinfunction "3_3") (pintype "unspecified"))
      (node (ref "R10") (pin "1") (pinfunction "1_1") (pintype "unspecified"))
      (node (ref "U1") (pin "37") (pinfunction "IO23_37") (pintype "unspecified"))
    )
    (net (code "38") (name "/TPSBOOT") (class "Default")
      (node (ref "C3") (pin "2") (pinfunction "2_2") (pintype "unspecified"))
      (node (ref "U8") (pin "1") (pinfunction "BOOT_1") (pintype "unspecified"))
    )
    (net (code "39") (name "/U0_RXD") (class "Default")
      (node (ref "CN1") (pin "15") (pinfunction "U0T_15") (pintype "unspecified"))
      (node (ref "U1") (pin "34") (pinfunction "RXD0_34") (pintype "unspecified"))
      (node (ref "U3") (pin "2") (pinfunction "TXD_2") (pintype "unspecified"))
    )
    (net (code "40") (name "/U0_TXD") (class "Default")
      (node (ref "CN1") (pin "14") (pinfunction "U0R_14") (pintype "unspecified"))
      (node (ref "U1") (pin "35") (pinfunction "TXD0_35") (pintype "unspecified"))
      (node (ref "U3") (pin "3") (pinfunction "RXD_3") (pintype "unspecified"))
    )
    (net (code "41") (name "DGND") (class "Default")
      (node (ref "C10") (pin "2") (pinfunction "2_2") (pintype "unspecified"))
      (node (ref "C11") (pin "2") (pinfunction "2_2") (pintype "unspecified"))
      (node (ref "C12") (pin "2") (pinfunction "2_2") (pintype "unspecified"))
      (node (ref "C13") (pin "1") (pinfunction "1_1") (pintype "unspecified"))
      (node (ref "C14") (pin "2") (pinfunction "2_2") (pintype "unspecified"))
      (node (ref "C15") (pin "1") (pinfunction "1_1") (pintype "unspecified"))
      (node (ref "C16") (pin "1") (pinfunction "1_1") (pintype "input"))
      (node (ref "C17") (pin "1") (pinfunction "1_1") (pintype "unspecified"))
      (node (ref "C28") (pin "1") (pinfunction "1_1") (pintype "unspecified"))
      (node (ref "C29") (pin "1") (pinfunction "1_1") (pintype "unspecified"))
      (node (ref "CN1") (pin "16") (pinfunction "GND_16") (pintype "unspecified"))
      (node (ref "CN1") (pin "7") (pinfunction "GND_7") (pintype "unspecified"))
      (node (ref "CN2") (pin "2") (pinfunction "2_2") (pintype "unspecified"))
      (node (ref "CN2") (pin "5") (pinfunction "5_5") (pintype "unspecified"))
      (node (ref "CN2") (pin "6") (pinfunction "6_6") (pintype "unspecified"))
      (node (ref "CN3") (pin "2") (pinfunction "2_2") (pintype "unspecified"))
      (node (ref "CN3") (pin "5") (pinfunction "5_5") (pintype "unspecified"))
      (node (ref "CN3") (pin "6") (pinfunction "6_6") (pintype "unspecified"))
      (node (ref "CN4") (pin "2") (pinfunction "2_2") (pintype "unspecified"))
      (node (ref "CN4") (pin "4") (pinfunction "4_4") (pintype "unspecified"))
      (node (ref "CN4") (pin "5") (pinfunction "5_5") (pintype "unspecified"))
      (node (ref "CN5") (pin "2") (pinfunction "2_2") (pintype "unspecified"))
      (node (ref "CN5") (pin "4") (pinfunction "4_4") (pintype "unspecified"))
      (node (ref "CN5") (pin "5") (pinfunction "5_5") (pintype "unspecified"))
      (node (ref "R7") (pin "2") (pinfunction "2_2") (pintype "unspecified"))
      (node (ref "U1") (pin "1") (pinfunction "GND_1") (pintype "unspecified"))
      (node (ref "U1") (pin "15") (pinfunction "GND_15") (pintype "unspecified"))
      (node (ref "U1") (pin "38") (pinfunction "GND_38") (pintype "unspecified"))
      (node (ref "U1") (pin "39") (pinfunction "GND_39") (pintype "unspecified"))
      (node (ref "U3") (pin "1") (pinfunction "GND_1") (pintype "unspecified"))
      (node (ref "U4") (pin "1") (pinfunction "CLKIN_1") (pintype "unspecified"))
      (node (ref "U4") (pin "11") (pinfunction "FSYNC_11") (pintype "unspecified"))
      (node (ref "U4") (pin "18") (pinfunction "GND_18") (pintype "unspecified"))
      (node (ref "U4") (pin "9") (pinfunction "AD0_9") (pintype "unspecified"))
    )
    (net (code "42") (name "Net-(D1-AK)") (class "Default")
      (node (ref "C23") (pin "2") (pinfunction "2_2") (pintype "input"))
      (node (ref "D1") (pin "3") (pinfunction "AK_3") (pintype "unspecified"))
    )
    (net (code "43") (name "Net-(D1-K)") (class "Default")
      (node (ref "C22") (pin "2") (pinfunction "2_2") (pintype "input"))
      (node (ref "D1") (pin "2") (pinfunction "K_2") (pintype "unspecified"))
      (node (ref "U5") (pin "18") (pinfunction "Vboot_18") (pintype "unspecified"))
    )
    (net (code "44") (name "Net-(D2-K)") (class "Default")
      (node (ref "C3") (pin "1") (pinfunction "1_1") (pintype "unspecified"))
      (node (ref "D2") (pin "2") (pinfunction "K_2") (pintype "unspecified"))
      (node (ref "L1") (pin "1") (pinfunction "1_1") (pintype "unspecified"))
      (node (ref "U8") (pin "8") (pinfunction "PH_8") (pintype "unspecified"))
    )
    (net (code "45") (name "Net-(D3-AK)") (class "Default")
      (node (ref "C25") (pin "2") (pinfunction "2_2") (pintype "input"))
      (node (ref "D3") (pin "3") (pinfunction "AK_3") (pintype "unspecified"))
    )
    (net (code "46") (name "Net-(D3-K)") (class "Default")
      (node (ref "C21") (pin "2") (pinfunction "2_2") (pintype "input"))
      (node (ref "D3") (pin "2") (pinfunction "K_2") (pintype "unspecified"))
      (node (ref "U2") (pin "18") (pinfunction "Vboot_18") (pintype "unspecified"))
    )
    (net (code "47") (name "Net-(LED3V3-Pad1)") (class "Default")
      (node (ref "LED3V3") (pin "1") (pinfunction "1_1") (pintype "unspecified"))
      (node (ref "R11") (pin "1") (pinfunction "1_1") (pintype "unspecified"))
    )
    (net (code "48") (name "Net-(Q1-B)") (class "Default")
      (node (ref "Q1") (pin "1") (pinfunction "B_1") (pintype "input"))
      (node (ref "R4") (pin "2") (pinfunction "2_2") (pintype "unspecified"))
    )
    (net (code "49") (name "Net-(Q3-B)") (class "Default")
      (node (ref "Q3") (pin "1") (pinfunction "B_1") (pintype "input"))
      (node (ref "R3") (pin "2") (pinfunction "2_2") (pintype "unspecified"))
    )
    (net (code "50") (name "Net-(U2-Vcp)") (class "Default")
      (node (ref "C25") (pin "1") (pinfunction "1_1") (pintype "input"))
      (node (ref "U2") (pin "17") (pinfunction "Vcp_17") (pintype "unspecified"))
    )
    (net (code "51") (name "Net-(U2-Vref)") (class "Default")
      (node (ref "C26") (pin "1") (pinfunction "1_1") (pintype "input"))
      (node (ref "U2") (pin "16") (pinfunction "Vref_16") (pintype "unspecified"))
    )
    (net (code "52") (name "Net-(U4-CPOUT)") (class "Default")
      (node (ref "C12") (pin "1") (pinfunction "1_1") (pintype "unspecified"))
      (node (ref "U4") (pin "20") (pinfunction "CPOUT_20") (pintype "unspecified"))
    )
    (net (code "53") (name "Net-(U4-REGOUT)") (class "Default")
      (node (ref "C11") (pin "1") (pinfunction "1_1") (pintype "unspecified"))
      (node (ref "U4") (pin "10") (pinfunction "REGOUT_10") (pintype "unspecified"))
    )
    (net (code "54") (name "Net-(U5-Vcp)") (class "Default")
      (node (ref "C23") (pin "1") (pinfunction "1_1") (pintype "input"))
      (node (ref "U5") (pin "17") (pinfunction "Vcp_17") (pintype "unspecified"))
    )
    (net (code "55") (name "Net-(U5-Vref)") (class "Default")
      (node (ref "C27") (pin "1") (pinfunction "1_1") (pintype "input"))
      (node (ref "U5") (pin "16") (pinfunction "Vref_16") (pintype "unspecified"))
    )
    (net (code "56") (name "Net-(U8-ENA)") (class "Default")
      (node (ref "SW2") (pin "2") (pinfunction "2_2") (pintype "unspecified"))
      (node (ref "U8") (pin "5") (pinfunction "ENA_5") (pintype "unspecified"))
    )
    (net (code "57") (name "Net-(U8-VSENSE)") (class "Default")
      (node (ref "R1") (pin "1") (pinfunction "1_1") (pintype "unspecified"))
      (node (ref "R2") (pin "2") (pinfunction "2_2") (pintype "unspecified"))
      (node (ref "U8") (pin "4") (pinfunction "VSENSE_4") (pintype "unspecified"))
    )
    (net (code "58") (name "PGND") (class "Default")
      (node (ref "C1") (pin "1") (pinfunction "1_1") (pintype "unspecified"))
      (node (ref "C18") (pin "1") (pinfunction "1_1") (pintype "unspecified"))
      (node (ref "C19") (pin "1") (pinfunction "1_1") (pintype "unspecified"))
      (node (ref "C2") (pin "2") (pinfunction "2_2") (pintype "input"))
      (node (ref "C20") (pin "2") (pinfunction "2_2") (pintype "input"))
      (node (ref "C24") (pin "2") (pinfunction "2_2") (pintype "input"))
      (node (ref "C26") (pin "2") (pinfunction "2_2") (pintype "input"))
      (node (ref "C27") (pin "2") (pinfunction "2_2") (pintype "input"))
      (node (ref "C30") (pin "2") (pinfunction "2_2") (pintype "input"))
      (node (ref "C31") (pin "1") (pinfunction "1_1") (pintype "unspecified"))
      (node (ref "C32") (pin "1") (pinfunction "1_1") (pintype "unspecified"))
      (node (ref "C33") (pin "1") (pinfunction "1_1") (pintype "unspecified"))
      (node (ref "C34") (pin "1") (pinfunction "1_1") (pintype "unspecified"))
      (node (ref "C4") (pin "2") (pinfunction "2_2") (pintype "input"))
      (node (ref "C5") (pin "2") (pinfunction "2_2") (pintype "input"))
      (node (ref "C6") (pin "1") (pinfunction "1_1") (pintype "unspecified"))
      (node (ref "C7") (pin "1") (pinfunction "1_1") (pintype "unspecified"))
      (node (ref "C8") (pin "1") (pinfunction "1_1") (pintype "unspecified"))
      (node (ref "C9") (pin "1") (pinfunction "1_1") (pintype "unspecified"))
      (node (ref "CN8") (pin "1") (pinfunction "1_1") (pintype "unspecified"))
      (node (ref "D2") (pin "1") (pinfunction "A_1") (pintype "unspecified"))
      (node (ref "KEY1") (pin "2") (pinfunction "2_2") (pintype "unspecified"))
      (node (ref "LED3V3") (pin "2") (pinfunction "2_2") (pintype "unspecified"))
      (node (ref "R13") (pin "2") (pinfunction "2_2") (pintype "unspecified"))
      (node (ref "R14") (pin "2") (pinfunction "2_2") (pintype "unspecified"))
      (node (ref "R2") (pin "1") (pinfunction "1_1") (pintype "unspecified"))
      (node (ref "R7") (pin "1") (pinfunction "1_1") (pintype "unspecified"))
      (node (ref "SW2") (pin "1") (pinfunction "1_1") (pintype "unspecified"))
      (node (ref "U10") (pin "4") (pinfunction "GND_4") (pintype "unspecified"))
      (node (ref "U10") (pin "7") (pinfunction "REF1_7") (pintype "unspecified"))
      (node (ref "U11") (pin "4") (pinfunction "GND_4") (pintype "unspecified"))
      (node (ref "U11") (pin "7") (pinfunction "REF1_7") (pintype "unspecified"))
      (node (ref "U2") (pin "1") (pinfunction "GND_1") (pintype "unspecified"))
      (node (ref "U2") (pin "10") (pinfunction "GND_10") (pintype "unspecified"))
      (node (ref "U2") (pin "11") (pinfunction "GND_11") (pintype "unspecified"))
      (node (ref "U2") (pin "19") (pinfunction "SENSE2_19") (pintype "unspecified"))
      (node (ref "U2") (pin "2") (pinfunction "SENSE1_2") (pintype "unspecified"))
      (node (ref "U2") (pin "20") (pinfunction "GND_20") (pintype "unspecified"))
      (node (ref "U2") (pin "21") (pinfunction "EP_21") (pintype "unspecified"))
      (node (ref "U5") (pin "1") (pinfunction "GND_1") (pintype "unspecified"))
      (node (ref "U5") (pin "10") (pinfunction "GND_10") (pintype "unspecified"))
      (node (ref "U5") (pin "11") (pinfunction "GND_11") (pintype "unspecified"))
      (node (ref "U5") (pin "19") (pinfunction "SENSE2_19") (pintype "unspecified"))
      (node (ref "U5") (pin "2") (pinfunction "SENSE1_2") (pintype "unspecified"))
      (node (ref "U5") (pin "20") (pinfunction "GND_20") (pintype "unspecified"))
      (node (ref "U5") (pin "21") (pinfunction "EP_21") (pintype "unspecified"))
      (node (ref "U6") (pin "1") (pinfunction "ADJ(GND)_1") (pintype "unspecified"))
      (node (ref "U7") (pin "4") (pinfunction "GND_4") (pintype "unspecified"))
      (node (ref "U7") (pin "7") (pinfunction "REF1_7") (pintype "unspecified"))
      (node (ref "U8") (pin "6") (pinfunction "GND_6") (pintype "unspecified"))
      (node (ref "U8") (pin "9") (pinfunction "PowerPAD_9") (pintype "unspecified"))
      (node (ref "U9") (pin "4") (pinfunction "GND_4") (pintype "unspecified"))
      (node (ref "U9") (pin "7") (pinfunction "REF1_7") (pintype "unspecified"))
      (node (ref "USB1") (pin "A1") (pinfunction "GND_A1") (pintype "unspecified"))
      (node (ref "USB1") (pin "A12") (pinfunction "GND_A12") (pintype "unspecified"))
    )
    (net (code "59") (name "unconnected-(CN1-3V3-Pad9)") (class "Default")
      (node (ref "CN1") (pin "9") (pinfunction "3V3_9") (pintype "unspecified+no_connect"))
    )
    (net (code "60") (name "unconnected-(CN1-GND-Pad12)") (class "Default")
      (node (ref "CN1") (pin "12") (pinfunction "GND_12") (pintype "unspecified+no_connect"))
    )
    (net (code "61") (name "unconnected-(CN1-IO0-Pad11)") (class "Default")
      (node (ref "CN1") (pin "11") (pinfunction "IO0_11") (pintype "unspecified+no_connect"))
    )
    (net (code "62") (name "unconnected-(CN1-IO2-Pad2)") (class "Default")
      (node (ref "CN1") (pin "2") (pinfunction "IO2_2") (pintype "unspecified+no_connect"))
    )
    (net (code "63") (name "unconnected-(CN1-IO4-Pad1)") (class "Default")
      (node (ref "CN1") (pin "1") (pinfunction "IO4_1") (pintype "unspecified+no_connect"))
    )
    (net (code "64") (name "unconnected-(CN1-IO12-Pad6)") (class "Default")
      (node (ref "CN1") (pin "6") (pinfunction "IO12_6") (pintype "unspecified+no_connect"))
    )
    (net (code "65") (name "unconnected-(CN1-IO13-Pad5)") (class "Default")
      (node (ref "CN1") (pin "5") (pinfunction "IO13_5") (pintype "unspecified+no_connect"))
    )
    (net (code "66") (name "unconnected-(CN1-IO14-Pad3)") (class "Default")
      (node (ref "CN1") (pin "3") (pinfunction "IO14_3") (pintype "unspecified+no_connect"))
    )
    (net (code "67") (name "unconnected-(CN1-IO15-Pad4)") (class "Default")
      (node (ref "CN1") (pin "4") (pinfunction "IO15_4") (pintype "unspecified+no_connect"))
    )
    (net (code "68") (name "unconnected-(CN1-IO16-Pad10)") (class "Default")
      (node (ref "CN1") (pin "10") (pinfunction "IO16_10") (pintype "unspecified+no_connect"))
    )
    (net (code "69") (name "unconnected-(CN1-VCC-Pad13)") (class "Default")
      (node (ref "CN1") (pin "13") (pinfunction "VCC_13") (pintype "unspecified+no_connect"))
    )
    (net (code "70") (name "unconnected-(M1-Pad1)") (class "Default")
      (node (ref "M1") (pin "1") (pinfunction "1_1") (pintype "unspecified+no_connect"))
    )
    (net (code "71") (name "unconnected-(M2-Pad1)") (class "Default")
      (node (ref "M2") (pin "1") (pinfunction "1_1") (pintype "unspecified+no_connect"))
    )
    (net (code "72") (name "unconnected-(M3-Pad1)") (class "Default")
      (node (ref "M3") (pin "1") (pinfunction "1_1") (pintype "unspecified+no_connect"))
    )
    (net (code "73") (name "unconnected-(M4-Pad1)") (class "Default")
      (node (ref "M4") (pin "1") (pinfunction "1_1") (pintype "unspecified+no_connect"))
    )
    (net (code "74") (name "unconnected-(SW2-Pad3)") (class "Default")
      (node (ref "SW2") (pin "3") (pinfunction "3_3") (pintype "unspecified"))
    )
    (net (code "75") (name "unconnected-(SW2-Pad4)") (class "Default")
      (node (ref "SW2") (pin "4") (pinfunction "4_4") (pintype "unspecified"))
    )
    (net (code "76") (name "unconnected-(SW2-Pad5)") (class "Default")
      (node (ref "SW2") (pin "5") (pinfunction "5_5") (pintype "unspecified"))
    )
    (net (code "77") (name "unconnected-(U1-CLK-Pad20)") (class "Default")
      (node (ref "U1") (pin "20") (pinfunction "CLK_20") (pintype "unspecified+no_connect"))
    )
    (net (code "78") (name "unconnected-(U1-CMD-Pad19)") (class "Default")
      (node (ref "U1") (pin "19") (pinfunction "CMD_19") (pintype "unspecified+no_connect"))
    )
    (net (code "79") (name "unconnected-(U1-IO2-Pad24)") (class "Default")
      (node (ref "U1") (pin "24") (pinfunction "IO2_24") (pintype "unspecified+no_connect"))
    )
    (net (code "80") (name "unconnected-(U1-IO4-Pad26)") (class "Default")
      (node (ref "U1") (pin "26") (pinfunction "IO4_26") (pintype "unspecified+no_connect"))
    )
    (net (code "81") (name "unconnected-(U1-IO13-Pad16)") (class "Default")
      (node (ref "U1") (pin "16") (pinfunction "IO13_16") (pintype "unspecified+no_connect"))
    )
    (net (code "82") (name "unconnected-(U1-IO15-Pad23)") (class "Default")
      (node (ref "U1") (pin "23") (pinfunction "IO15_23") (pintype "unspecified+no_connect"))
    )
    (net (code "83") (name "unconnected-(U1-IO21-Pad33)") (class "Default")
      (node (ref "U1") (pin "33") (pinfunction "IO21_33") (pintype "unspecified+no_connect"))
    )
    (net (code "84") (name "unconnected-(U1-NC-Pad32)") (class "Default")
      (node (ref "U1") (pin "32") (pinfunction "NC_32") (pintype "unspecified+no_connect"))
    )
    (net (code "85") (name "unconnected-(U1-SD0-Pad21)") (class "Default")
      (node (ref "U1") (pin "21") (pinfunction "SD0_21") (pintype "unspecified+no_connect"))
    )
    (net (code "86") (name "unconnected-(U1-SD1-Pad22)") (class "Default")
      (node (ref "U1") (pin "22") (pinfunction "SD1_22") (pintype "unspecified+no_connect"))
    )
    (net (code "87") (name "unconnected-(U1-SD2-Pad17)") (class "Default")
      (node (ref "U1") (pin "17") (pinfunction "SD2_17") (pintype "unspecified+no_connect"))
    )
    (net (code "88") (name "unconnected-(U1-SD3-Pad18)") (class "Default")
      (node (ref "U1") (pin "18") (pinfunction "SD3_18") (pintype "unspecified+no_connect"))
    )
    (net (code "89") (name "unconnected-(U3-CTS#-Pad9)") (class "Default")
      (node (ref "U3") (pin "9") (pinfunction "CTS#_9") (pintype "unspecified+no_connect"))
    )
    (net (code "90") (name "unconnected-(U3-DCD#-Pad12)") (class "Default")
      (node (ref "U3") (pin "12") (pinfunction "DCD#_12") (pintype "unspecified+no_connect"))
    )
    (net (code "91") (name "unconnected-(U3-DSR#-Pad10)") (class "Default")
      (node (ref "U3") (pin "10") (pinfunction "DSR#_10") (pintype "unspecified+no_connect"))
    )
    (net (code "92") (name "unconnected-(U3-NC.-Pad7)") (class "Default")
      (node (ref "U3") (pin "7") (pinfunction "NC._7") (pintype "unspecified+no_connect"))
    )
    (net (code "93") (name "unconnected-(U3-NC.-Pad8)") (class "Default")
      (node (ref "U3") (pin "8") (pinfunction "NC._8") (pintype "unspecified+no_connect"))
    )
    (net (code "94") (name "unconnected-(U3-R232-Pad15)") (class "Default")
      (node (ref "U3") (pin "15") (pinfunction "R232_15") (pintype "unspecified+no_connect"))
    )
    (net (code "95") (name "unconnected-(U3-RI#-Pad11)") (class "Default")
      (node (ref "U3") (pin "11") (pinfunction "RI#_11") (pintype "unspecified+no_connect"))
    )
    (net (code "96") (name "unconnected-(U4-AUX_CL-Pad7)") (class "Default")
      (node (ref "U4") (pin "7") (pinfunction "AUX_CL_7") (pintype "unspecified+no_connect"))
    )
    (net (code "97") (name "unconnected-(U4-AUX_DA-Pad6)") (class "Default")
      (node (ref "U4") (pin "6") (pinfunction "AUX_DA_6") (pintype "unspecified+no_connect"))
    )
    (net (code "98") (name "unconnected-(U4-INT-Pad12)") (class "Default")
      (node (ref "U4") (pin "12") (pinfunction "INT_12") (pintype "unspecified+no_connect"))
    )
    (net (code "99") (name "unconnected-(U4-NC-Pad2)") (class "Default")
      (node (ref "U4") (pin "2") (pinfunction "NC_2") (pintype "unspecified+no_connect"))
    )
    (net (code "100") (name "unconnected-(U4-NC-Pad3)") (class "Default")
      (node (ref "U4") (pin "3") (pinfunction "NC_3") (pintype "unspecified+no_connect"))
    )
    (net (code "101") (name "unconnected-(U4-NC-Pad4)") (class "Default")
      (node (ref "U4") (pin "4") (pinfunction "NC_4") (pintype "unspecified+no_connect"))
    )
    (net (code "102") (name "unconnected-(U4-NC-Pad5)") (class "Default")
      (node (ref "U4") (pin "5") (pinfunction "NC_5") (pintype "unspecified+no_connect"))
    )
    (net (code "103") (name "unconnected-(U4-NC-Pad14)") (class "Default")
      (node (ref "U4") (pin "14") (pinfunction "NC_14") (pintype "unspecified+no_connect"))
    )
    (net (code "104") (name "unconnected-(U4-NC-Pad15)") (class "Default")
      (node (ref "U4") (pin "15") (pinfunction "NC_15") (pintype "unspecified+no_connect"))
    )
    (net (code "105") (name "unconnected-(U4-NC-Pad16)") (class "Default")
      (node (ref "U4") (pin "16") (pinfunction "NC_16") (pintype "unspecified+no_connect"))
    )
    (net (code "106") (name "unconnected-(U4-NC-Pad17)") (class "Default")
      (node (ref "U4") (pin "17") (pinfunction "NC_17") (pintype "unspecified+no_connect"))
    )
    (net (code "107") (name "unconnected-(U4-RESV-Pad19)") (class "Default")
      (node (ref "U4") (pin "19") (pinfunction "RESV_19") (pintype "unspecified+no_connect"))
    )
    (net (code "108") (name "unconnected-(U4-RESV-Pad21)") (class "Default")
      (node (ref "U4") (pin "21") (pinfunction "RESV_21") (pintype "unspecified+no_connect"))
    )
    (net (code "109") (name "unconnected-(U4-RESV-Pad22)") (class "Default")
      (node (ref "U4") (pin "22") (pinfunction "RESV_22") (pintype "unspecified+no_connect"))
    )
    (net (code "110") (name "unconnected-(U7-NC-Pad1)") (class "Default")
      (node (ref "U7") (pin "1") (pinfunction "NC_1") (pintype "unspecified+no_connect"))
    )
    (net (code "111") (name "unconnected-(U8-NC-Pad2)") (class "Default")
      (node (ref "U8") (pin "2") (pinfunction "NC_2") (pintype "unspecified+no_connect"))
    )
    (net (code "112") (name "unconnected-(U8-NC-Pad3)") (class "Default")
      (node (ref "U8") (pin "3") (pinfunction "NC_3") (pintype "unspecified+no_connect"))
    )
    (net (code "113") (name "unconnected-(U9-NC-Pad1)") (class "Default")
      (node (ref "U9") (pin "1") (pinfunction "NC_1") (pintype "unspecified+no_connect"))
    )
    (net (code "114") (name "unconnected-(U10-NC-Pad1)") (class "Default")
      (node (ref "U10") (pin "1") (pinfunction "NC_1") (pintype "unspecified+no_connect"))
    )
    (net (code "115") (name "unconnected-(U11-NC-Pad1)") (class "Default")
      (node (ref "U11") (pin "1") (pinfunction "NC_1") (pintype "unspecified+no_connect"))
    )
    (net (code "116") (name "unconnected-(USB1-CC1-PadA5)") (class "Default")
      (node (ref "USB1") (pin "A5") (pinfunction "CC1_A5") (pintype "unspecified+no_connect"))
    )
    (net (code "117") (name "unconnected-(USB1-CC2-PadB5)") (class "Default")
      (node (ref "USB1") (pin "B5") (pinfunction "CC2_B5") (pintype "unspecified+no_connect"))
    )
    (net (code "118") (name "unconnected-(USB1-Pad1)") (class "Default")
      (node (ref "USB1") (pin "1") (pinfunction "1_1") (pintype "unspecified+no_connect"))
    )
    (net (code "119") (name "unconnected-(USB1-SBU1-PadA8)") (class "Default")
      (node (ref "USB1") (pin "A8") (pinfunction "SBU1_A8") (pintype "unspecified+no_connect"))
    )
    (net (code "120") (name "unconnected-(USB1-SBU2-PadB8)") (class "Default")
      (node (ref "USB1") (pin "B8") (pinfunction "SBU2_B8") (pintype "unspecified+no_connect"))
    )
  )
)
